# Microcontroller.net
KiCad netlist of a schematic drawn in Altium Designer
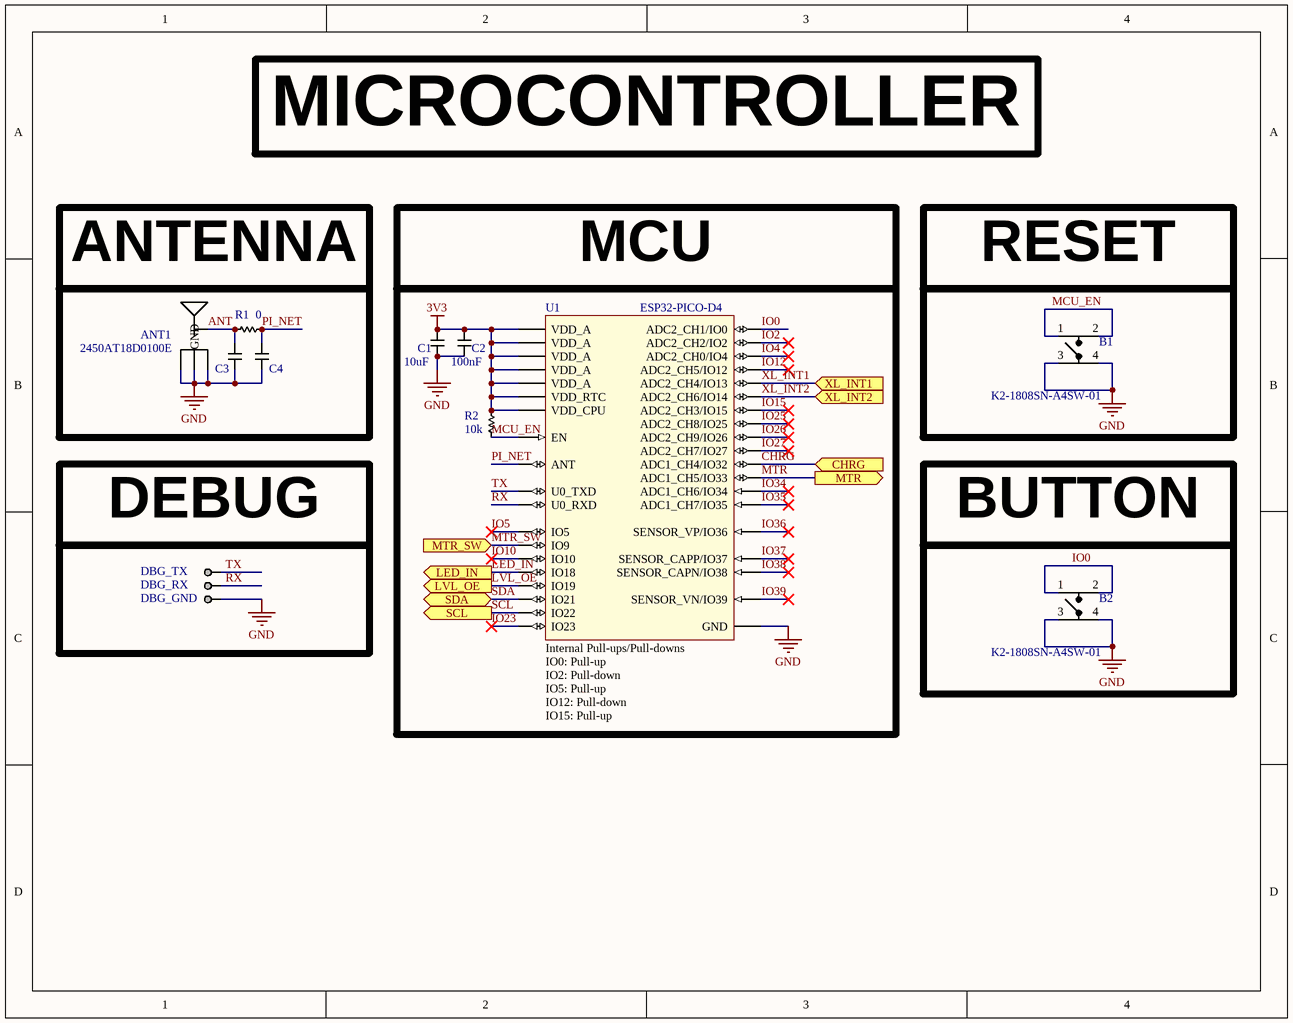
[diagram p0: Microcontroller.SchDoc]

(export (version "E")
  (design (tool "Eeschema 10.0.6"))
  (components
    (comp (ref "ANT1")
      (value "2450AT18D0100E")
      (footprint "2450AT18D0100E_RH")
      (description "2450AT18D0100E 2.4GHz  Chip RF Antenna 2.4GHz ~ 2.5GHz 1.5dBi Solder Surface Mount")
      (libsource (lib "smLib") (part "2450AT18D0100E_RH"))
    )
    (comp (ref "B1")
      (value "K2-1808SN-A4SW-01")
      (footprint "K2-1808SN-A4SW-01")
      (description "K2-1808SN-A4SW-01 Tactile Switch SPST-NO Top Actuated Surface Mount")
      (libsource (lib "smLib") (part "K2-1808SN-A4SW-01"))
    )
    (comp (ref "B2")
      (value "K2-1808SN-A4SW-01")
      (footprint "K2-1808SN-A4SW-01")
      (description "K2-1808SN-A4SW-01 Tactile Switch SPST-NO Top Actuated Surface Mount")
      (libsource (lib "smLib") (part "K2-1808SN-A4SW-01"))
    )
    (comp (ref "C1")
      (value "10uF")
      (footprint "CAP_0603_HIGH")
      (description "0603 Capacitor")
      (libsource (lib "smLib") (part "Capacitor_0603"))
    )
    (comp (ref "C2")
      (value "100nF")
      (footprint "CAP_0402_HIGH")
      (description "0402 Capacitor")
      (libsource (lib "smLib") (part "Capacitor_0402"))
    )
    (comp (ref "C3")
      (value "C")
      (footprint "CAP_0402_HIGH")
      (description "0402 Capacitor")
      (libsource (lib "smLib") (part "Capacitor_0402"))
    )
    (comp (ref "C4")
      (value "C")
      (footprint "CAP_0402_HIGH")
      (description "0402 Capacitor")
      (libsource (lib "smLib") (part "Capacitor_0402"))
    )
    (comp (ref "DBG_GND")
      (value "0.1\" Header")
      (footprint "0.1\" Header")
      (libsource (lib "smLib") (part "0.1{dblquote} Header"))
    )
    (comp (ref "DBG_RX")
      (value "0.1\" Header")
      (footprint "0.1\" Header")
      (libsource (lib "smLib") (part "0.1{dblquote} Header"))
    )
    (comp (ref "DBG_TX")
      (value "0.1\" Header")
      (footprint "0.1\" Header")
      (libsource (lib "smLib") (part "0.1{dblquote} Header"))
    )
    (comp (ref "R1")
      (value "0")
      (footprint "RES_0402_HIGH")
      (description "0402 Resistor")
      (libsource (lib "smLib") (part "Resistor_0402"))
    )
    (comp (ref "R2")
      (value "10k")
      (footprint "RES_0402_HIGH")
      (description "0402 Resistor")
      (libsource (lib "smLib") (part "Resistor_0402"))
    )
    (comp (ref "U1")
      (value "ESP32-PICO-D4")
      (footprint "ESP32-PICO-D4")
      (description "ESP32-PICO-D4 SoC")
      (libsource (lib "smLib") (part "ESP32-PICO-D4"))
    )
  )
  (nets
    (net (code "1") (name "/ANT") (class "Default")
      (node (ref "ANT1") (pin "1") (pinfunction "FEED_1") (pintype "passive"))
      (node (ref "C3") (pin "2") (pinfunction "2_2") (pintype "passive"))
      (node (ref "R1") (pin "1") (pinfunction "1_1") (pintype "passive"))
    )
    (net (code "2") (name "/CHRG") (class "Default")
      (node (ref "U1") (pin "12") (pinfunction "ADC1_CH4/IO32_12") (pintype "bidirectional"))
    )
    (net (code "3") (name "/IO0") (class "Default")
      (node (ref "B2") (pin "1") (pinfunction "1_1") (pintype "passive"))
      (node (ref "B2") (pin "2") (pinfunction "2_2") (pintype "passive"))
      (node (ref "U1") (pin "23") (pinfunction "ADC2_CH1/IO0_23") (pintype "bidirectional"))
    )
    (net (code "4") (name "/IO2") (class "Default")
      (node (ref "U1") (pin "22") (pinfunction "ADC2_CH2/IO2_22") (pintype "bidirectional+no_connect"))
    )
    (net (code "5") (name "/IO4") (class "Default")
      (node (ref "U1") (pin "24") (pinfunction "ADC2_CH0/IO4_24") (pintype "bidirectional+no_connect"))
    )
    (net (code "6") (name "/IO5") (class "Default")
      (node (ref "U1") (pin "34") (pinfunction "IO5_34") (pintype "bidirectional+no_connect"))
    )
    (net (code "7") (name "/IO10") (class "Default")
      (node (ref "U1") (pin "29") (pinfunction "IO10_29") (pintype "bidirectional+no_connect"))
    )
    (net (code "8") (name "/IO12") (class "Default")
      (node (ref "U1") (pin "18") (pinfunction "ADC2_CH5/IO12_18") (pintype "bidirectional+no_connect"))
    )
    (net (code "9") (name "/IO15") (class "Default")
      (node (ref "U1") (pin "21") (pinfunction "ADC2_CH3/IO15_21") (pintype "bidirectional+no_connect"))
    )
    (net (code "10") (name "/IO23") (class "Default")
      (node (ref "U1") (pin "36") (pinfunction "IO23_36") (pintype "bidirectional+no_connect"))
    )
    (net (code "11") (name "/IO25") (class "Default")
      (node (ref "U1") (pin "14") (pinfunction "ADC2_CH8/IO25_14") (pintype "bidirectional+no_connect"))
    )
    (net (code "12") (name "/IO26") (class "Default")
      (node (ref "U1") (pin "15") (pinfunction "ADC2_CH9/IO26_15") (pintype "bidirectional+no_connect"))
    )
    (net (code "13") (name "/IO27") (class "Default")
      (node (ref "U1") (pin "16") (pinfunction "ADC2_CH7/IO27_16") (pintype "bidirectional+no_connect"))
    )
    (net (code "14") (name "/IO34") (class "Default")
      (node (ref "U1") (pin "10") (pinfunction "ADC1_CH6/IO34_10") (pintype "input+no_connect"))
    )
    (net (code "15") (name "/IO35") (class "Default")
      (node (ref "U1") (pin "11") (pinfunction "ADC1_CH7/IO35_11") (pintype "input+no_connect"))
    )
    (net (code "16") (name "/IO36") (class "Default")
      (node (ref "U1") (pin "5") (pinfunction "SENSOR_VP/IO36_5") (pintype "input+no_connect"))
    )
    (net (code "17") (name "/IO37") (class "Default")
      (node (ref "U1") (pin "6") (pinfunction "SENSOR_CAPP/IO37_6") (pintype "input+no_connect"))
    )
    (net (code "18") (name "/IO38") (class "Default")
      (node (ref "U1") (pin "7") (pinfunction "SENSOR_CAPN/IO38_7") (pintype "input+no_connect"))
    )
    (net (code "19") (name "/IO39") (class "Default")
      (node (ref "U1") (pin "8") (pinfunction "SENSOR_VN/IO39_8") (pintype "input+no_connect"))
    )
    (net (code "20") (name "/LED_IN") (class "Default")
      (node (ref "U1") (pin "35") (pinfunction "IO18_35") (pintype "bidirectional"))
    )
    (net (code "21") (name "/LVL_OE") (class "Default")
      (node (ref "U1") (pin "38") (pinfunction "IO19_38") (pintype "bidirectional"))
    )
    (net (code "22") (name "/MCU_EN") (class "Default")
      (node (ref "B1") (pin "1") (pinfunction "1_1") (pintype "passive"))
      (node (ref "B1") (pin "2") (pinfunction "2_2") (pintype "passive"))
      (node (ref "R2") (pin "1") (pinfunction "1_1") (pintype "passive"))
      (node (ref "U1") (pin "9") (pinfunction "EN_9") (pintype "input"))
    )
    (net (code "23") (name "/MTR") (class "Default")
      (node (ref "U1") (pin "13") (pinfunction "ADC1_CH5/IO33_13") (pintype "bidirectional"))
    )
    (net (code "24") (name "/MTR_SW") (class "Default")
      (node (ref "U1") (pin "28") (pinfunction "IO9_28") (pintype "bidirectional"))
    )
    (net (code "25") (name "/PI_NET") (class "Default")
      (node (ref "C4") (pin "2") (pinfunction "2_2") (pintype "passive"))
      (node (ref "R1") (pin "2") (pinfunction "2_2") (pintype "passive"))
      (node (ref "U1") (pin "2") (pinfunction "ANT_2") (pintype "bidirectional"))
    )
    (net (code "26") (name "/RX") (class "Default")
      (node (ref "DBG_RX") (pin "1") (pinfunction "1_1") (pintype "passive"))
      (node (ref "U1") (pin "40") (pinfunction "U0_RXD_40") (pintype "bidirectional"))
    )
    (net (code "27") (name "/SCL") (class "Default")
      (node (ref "U1") (pin "39") (pinfunction "IO22_39") (pintype "bidirectional"))
    )
    (net (code "28") (name "/SDA") (class "Default")
      (node (ref "U1") (pin "42") (pinfunction "IO21_42") (pintype "bidirectional"))
    )
    (net (code "29") (name "/TX") (class "Default")
      (node (ref "DBG_TX") (pin "1") (pinfunction "1_1") (pintype "passive"))
      (node (ref "U1") (pin "41") (pinfunction "U0_TXD_41") (pintype "bidirectional"))
    )
    (net (code "30") (name "/XL_INT1") (class "Default")
      (node (ref "U1") (pin "20") (pinfunction "ADC2_CH4/IO13_20") (pintype "bidirectional"))
    )
    (net (code "31") (name "/XL_INT2") (class "Default")
      (node (ref "U1") (pin "17") (pinfunction "ADC2_CH6/IO14_17") (pintype "bidirectional"))
    )
    (net (code "32") (name "3V3") (class "Default")
      (node (ref "C1") (pin "2") (pinfunction "2_2") (pintype "passive"))
      (node (ref "C2") (pin "2") (pinfunction "2_2") (pintype "passive"))
      (node (ref "R2") (pin "2") (pinfunction "2_2") (pintype "passive"))
      (node (ref "U1") (pin "1") (pinfunction "VDD_A_1") (pintype "power_in"))
      (node (ref "U1") (pin "19") (pinfunction "VDD_RTC_19") (pintype "power_in"))
      (node (ref "U1") (pin "3") (pinfunction "VDD_A_3") (pintype "power_in"))
      (node (ref "U1") (pin "37") (pinfunction "VDD_CPU_37") (pintype "power_in"))
      (node (ref "U1") (pin "4") (pinfunction "VDD_A_4") (pintype "power_in"))
      (node (ref "U1") (pin "43") (pinfunction "VDD_A_43") (pintype "power_in"))
      (node (ref "U1") (pin "46") (pinfunction "VDD_A_46") (pintype "power_in"))
    )
    (net (code "33") (name "GND") (class "Default")
      (node (ref "ANT1") (pin "2") (pinfunction "GND_2") (pintype "passive"))
      (node (ref "ANT1") (pin "3") (pinfunction "GND_3") (pintype "passive"))
      (node (ref "ANT1") (pin "4") (pinfunction "GND_4") (pintype "passive"))
      (node (ref "B1") (pin "3") (pinfunction "3_3") (pintype "passive"))
      (node (ref "B1") (pin "4") (pinfunction "4_4") (pintype "passive"))
      (node (ref "B2") (pin "3") (pinfunction "3_3") (pintype "passive"))
      (node (ref "B2") (pin "4") (pinfunction "4_4") (pintype "passive"))
      (node (ref "C1") (pin "1") (pinfunction "1_1") (pintype "passive"))
      (node (ref "C2") (pin "1") (pinfunction "1_1") (pintype "passive"))
      (node (ref "C3") (pin "1") (pinfunction "1_1") (pintype "passive"))
      (node (ref "C4") (pin "1") (pinfunction "1_1") (pintype "passive"))
      (node (ref "DBG_GND") (pin "1") (pinfunction "1_1") (pintype "passive"))
      (node (ref "U1") (pin "49") (pinfunction "GND_49") (pintype "power_in"))
    )
  )
)
